# CAN-Bus_Shield_v1_2.net
KiCad netlist of a schematic drawn in EAGLE
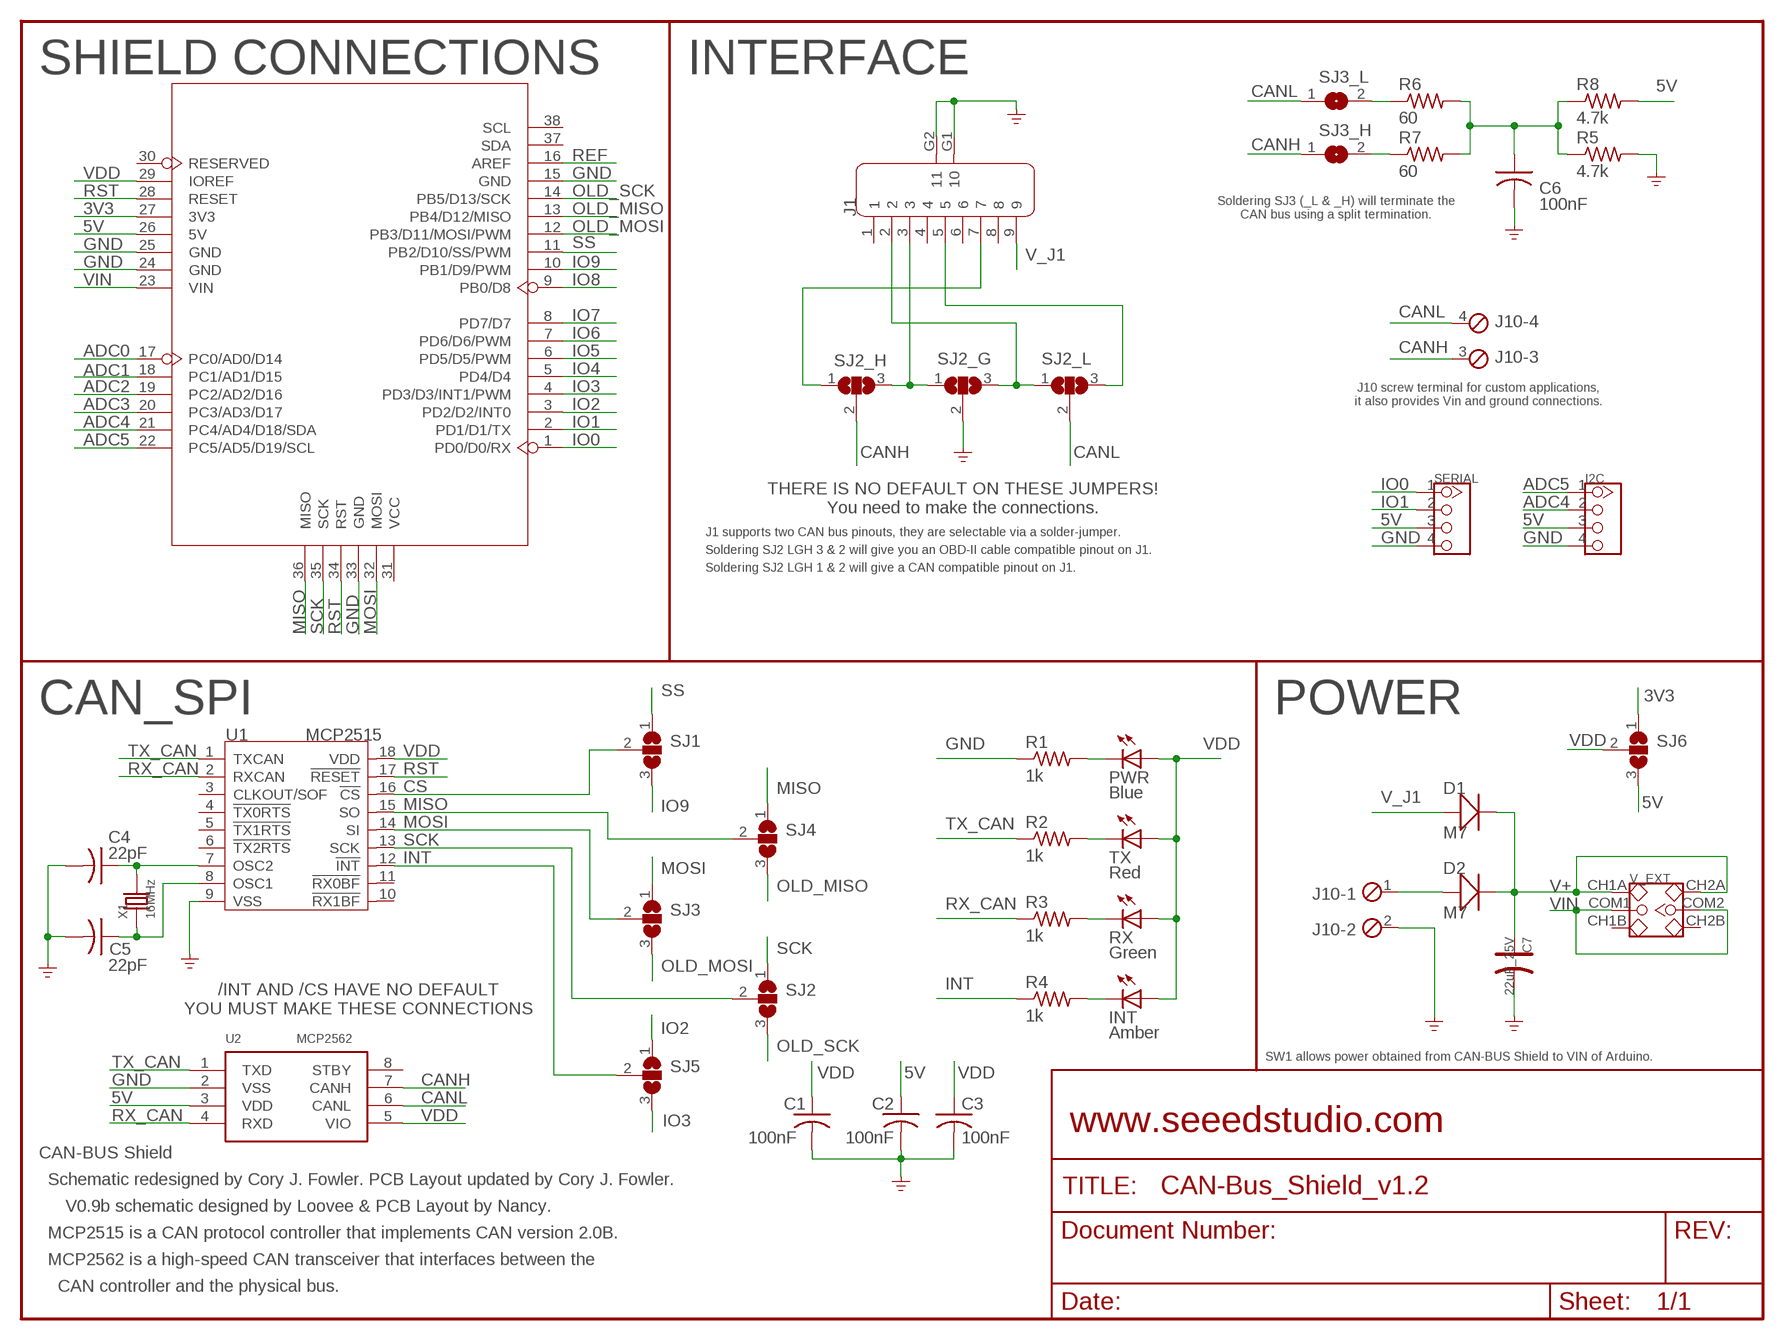
[diagram p0: schematic, sheet 1]

(export (version "E")
  (design (tool "Eeschema 10.0.6"))
  (components
    (comp (ref "C1")
      (value "100nF")
      (footprint "eagle-import:C0603K")
      (libsource (lib "eagle-import") (part "C-USC0603K"))
    )
    (comp (ref "C2")
      (value "100nF")
      (footprint "eagle-import:C0603K")
      (libsource (lib "eagle-import") (part "C-USC0603K"))
    )
    (comp (ref "C3")
      (value "100nF")
      (footprint "eagle-import:C0603K")
      (libsource (lib "eagle-import") (part "C-USC0603K"))
    )
    (comp (ref "C4")
      (value "22pF")
      (footprint "eagle-import:C0603")
      (libsource (lib "eagle-import") (part "C-USC0603"))
    )
    (comp (ref "C5")
      (value "22pF")
      (footprint "eagle-import:C0603")
      (libsource (lib "eagle-import") (part "C-USC0603"))
    )
    (comp (ref "C6")
      (value "100nF")
      (footprint "eagle-import:C1210")
      (libsource (lib "eagle-import") (part "C-USC1210"))
    )
    (comp (ref "C7")
      (value "22uF_25V")
      (footprint "eagle-import:AVX-C")
      (libsource (lib "eagle-import") (part "CAP-AVX-C"))
    )
    (comp (ref "D1")
      (value "M7")
      (footprint "eagle-import:D2010")
      (libsource (lib "eagle-import") (part "D-SMA"))
    )
    (comp (ref "D2")
      (value "M7")
      (footprint "eagle-import:D2010")
      (libsource (lib "eagle-import") (part "D-SMA"))
    )
    (comp (ref "I2C")
      (value "TWIG-4P-2.0-2.0")
      (footprint "eagle-import:4P-2.0")
      (libsource (lib "eagle-import") (part "TWIG-4P-2.0-2.0"))
    )
    (comp (ref "INT")
      (value "Amber")
      (footprint "eagle-import:CHIP-LED0805")
      (libsource (lib "eagle-import") (part "LEDCHIP-LED0805"))
    )
    (comp (ref "J1")
      (value "DB9'MEAL'")
      (footprint "eagle-import:DB9-MEAL")
      (libsource (lib "eagle-import") (part "DB9'MEAL'"))
    )
    (comp (ref "J10")
      (value "MPT4")
      (footprint "eagle-import:4POL254")
      (libsource (lib "eagle-import") (part "MPT4"))
    )
    (comp (ref "PWR")
      (value "Blue")
      (footprint "eagle-import:CHIP-LED0805")
      (libsource (lib "eagle-import") (part "LEDCHIP-LED0805"))
    )
    (comp (ref "R1")
      (value "1k")
      (footprint "eagle-import:M0805")
      (libsource (lib "eagle-import") (part "R-US_M0805"))
    )
    (comp (ref "R2")
      (value "1k")
      (footprint "eagle-import:M0805")
      (libsource (lib "eagle-import") (part "R-US_M0805"))
    )
    (comp (ref "R3")
      (value "1k")
      (footprint "eagle-import:M0805")
      (libsource (lib "eagle-import") (part "R-US_M0805"))
    )
    (comp (ref "R4")
      (value "1k")
      (footprint "eagle-import:M0805")
      (libsource (lib "eagle-import") (part "R-US_M0805"))
    )
    (comp (ref "R5")
      (value "4.7k")
      (footprint "eagle-import:M3216")
      (libsource (lib "eagle-import") (part "R-US_M3216"))
    )
    (comp (ref "R6")
      (value "60")
      (footprint "eagle-import:M3216")
      (libsource (lib "eagle-import") (part "R-US_M3216"))
    )
    (comp (ref "R7")
      (value "60")
      (footprint "eagle-import:M3216")
      (libsource (lib "eagle-import") (part "R-US_M3216"))
    )
    (comp (ref "R8")
      (value "4.7k")
      (footprint "eagle-import:M3216")
      (libsource (lib "eagle-import") (part "R-US_M3216"))
    )
    (comp (ref "RX")
      (value "Green")
      (footprint "eagle-import:CHIP-LED0805")
      (libsource (lib "eagle-import") (part "LEDCHIP-LED0805"))
    )
    (comp (ref "SERIAL")
      (value "TWIG-4P-2.0-2.0")
      (footprint "eagle-import:4P-2.0")
      (libsource (lib "eagle-import") (part "TWIG-4P-2.0-2.0"))
    )
    (comp (ref "SJ1")
      (value "SJ2W")
      (footprint "eagle-import:SJ_2")
      (libsource (lib "eagle-import") (part "SJ2W"))
    )
    (comp (ref "SJ2")
      (value "SJ2W")
      (footprint "eagle-import:SJ_2")
      (libsource (lib "eagle-import") (part "SJ2W"))
    )
    (comp (ref "SJ2_G")
      (value "SJ2W")
      (footprint "eagle-import:SJ_2")
      (libsource (lib "eagle-import") (part "SJ2W"))
    )
    (comp (ref "SJ2_H")
      (value "SJ2W")
      (footprint "eagle-import:SJ_2")
      (libsource (lib "eagle-import") (part "SJ2W"))
    )
    (comp (ref "SJ2_L")
      (value "SJ2W")
      (footprint "eagle-import:SJ_2")
      (libsource (lib "eagle-import") (part "SJ2W"))
    )
    (comp (ref "SJ3")
      (value "SJ2W")
      (footprint "eagle-import:SJ_2")
      (libsource (lib "eagle-import") (part "SJ2W"))
    )
    (comp (ref "SJ3_H")
      (value "SJ")
      (footprint "eagle-import:SJ")
      (libsource (lib "eagle-import") (part "SJ"))
    )
    (comp (ref "SJ3_L")
      (value "SJ")
      (footprint "eagle-import:SJ")
      (libsource (lib "eagle-import") (part "SJ"))
    )
    (comp (ref "SJ4")
      (value "SJ2W")
      (footprint "eagle-import:SJ_2")
      (libsource (lib "eagle-import") (part "SJ2W"))
    )
    (comp (ref "SJ5")
      (value "SJ2W")
      (footprint "eagle-import:SJ_2")
      (libsource (lib "eagle-import") (part "SJ2W"))
    )
    (comp (ref "SJ6")
      (value "SJ2W")
      (footprint "eagle-import:SJ_2")
      (libsource (lib "eagle-import") (part "SJ2W"))
    )
    (comp (ref "TX")
      (value "Red")
      (footprint "eagle-import:CHIP-LED0805")
      (libsource (lib "eagle-import") (part "LEDCHIP-LED0805"))
    )
    (comp (ref "U1")
      (value "MCP2515")
      (footprint "eagle-import:SOIC18")
      (libsource (lib "eagle-import") (part "MCP2515"))
    )
    (comp (ref "U2")
      (value "MCP2562")
      (footprint "eagle-import:SO08")
      (libsource (lib "eagle-import") (part "MCP2562"))
    )
    (comp (ref "U3")
      (value "ARDUINO")
      (footprint "eagle-import:ARDUINO")
      (libsource (lib "eagle-import") (part "ARDUINO"))
    )
    (comp (ref "V_EXT")
      (value "SWITCH-2CH-6P")
      (footprint "eagle-import:6P-2CH-2.54-7.6X3.0")
      (libsource (lib "eagle-import") (part "SWITCH-2CH-6P"))
    )
    (comp (ref "X1")
      (value "16MHz")
      (footprint "eagle-import:HC49_S")
      (libsource (lib "eagle-import") (part "CRYSTAL-HC49S"))
    )
  )
  (nets
    (net (code "1") (name "/3V3") (class "Default")
      (node (ref "SJ6") (pin "1") (pinfunction "1_1") (pintype "passive"))
      (node (ref "U3") (pin "27") (pinfunction "3V3_27") (pintype "bidirectional"))
    )
    (net (code "2") (name "/5V") (class "Default")
      (node (ref "C2") (pin "1") (pinfunction "1_1") (pintype "passive"))
      (node (ref "I2C") (pin "3") (pinfunction "3_3") (pintype "bidirectional"))
      (node (ref "R8") (pin "2") (pinfunction "2_2") (pintype "passive"))
      (node (ref "SERIAL") (pin "3") (pinfunction "3_3") (pintype "bidirectional"))
      (node (ref "SJ6") (pin "3") (pinfunction "3_3") (pintype "passive"))
      (node (ref "U2") (pin "3") (pinfunction "VDD_3") (pintype "bidirectional"))
      (node (ref "U3") (pin "26") (pinfunction "5V_26") (pintype "bidirectional"))
    )
    (net (code "3") (name "/ADC0") (class "Default")
      (node (ref "U3") (pin "17") (pinfunction "PC0/AD0/D14_17") (pintype "bidirectional"))
    )
    (net (code "4") (name "/ADC1") (class "Default")
      (node (ref "U3") (pin "18") (pinfunction "PC1/AD1/D15_18") (pintype "bidirectional"))
    )
    (net (code "5") (name "/ADC2") (class "Default")
      (node (ref "U3") (pin "19") (pinfunction "PC2/AD2/D16_19") (pintype "bidirectional"))
    )
    (net (code "6") (name "/ADC3") (class "Default")
      (node (ref "U3") (pin "20") (pinfunction "PC3/AD3/D17_20") (pintype "bidirectional"))
    )
    (net (code "7") (name "/ADC4") (class "Default")
      (node (ref "I2C") (pin "2") (pinfunction "2_2") (pintype "bidirectional"))
      (node (ref "U3") (pin "21") (pinfunction "PC4/AD4/D18/SDA_21") (pintype "bidirectional"))
    )
    (net (code "8") (name "/ADC5") (class "Default")
      (node (ref "I2C") (pin "1") (pinfunction "1_1") (pintype "bidirectional"))
      (node (ref "U3") (pin "22") (pinfunction "PC5/AD5/D19/SCL_22") (pintype "bidirectional"))
    )
    (net (code "9") (name "/CANH") (class "Default")
      (node (ref "J10") (pin "3") (pinfunction "1_3") (pintype "passive"))
      (node (ref "SJ2_H") (pin "2") (pinfunction "2_2") (pintype "passive"))
      (node (ref "SJ3_H") (pin "1") (pinfunction "1_1") (pintype "passive"))
      (node (ref "U2") (pin "7") (pinfunction "CANH_7") (pintype "bidirectional"))
    )
    (net (code "10") (name "/CANL") (class "Default")
      (node (ref "J10") (pin "4") (pinfunction "1_4") (pintype "passive"))
      (node (ref "SJ2_L") (pin "2") (pinfunction "2_2") (pintype "passive"))
      (node (ref "SJ3_L") (pin "1") (pinfunction "1_1") (pintype "passive"))
      (node (ref "U2") (pin "6") (pinfunction "CANL_6") (pintype "bidirectional"))
    )
    (net (code "11") (name "/CS") (class "Default")
      (node (ref "SJ1") (pin "2") (pinfunction "2_2") (pintype "passive"))
      (node (ref "U1") (pin "16") (pinfunction "~{CS}_16") (pintype "input"))
    )
    (net (code "12") (name "/INT") (class "Default")
      (node (ref "R4") (pin "1") (pinfunction "1_1") (pintype "passive"))
      (node (ref "SJ5") (pin "2") (pinfunction "2_2") (pintype "passive"))
      (node (ref "U1") (pin "12") (pinfunction "~{INT}_12") (pintype "output"))
    )
    (net (code "13") (name "/IO0") (class "Default")
      (node (ref "SERIAL") (pin "1") (pinfunction "1_1") (pintype "bidirectional"))
      (node (ref "U3") (pin "1") (pinfunction "PD0/D0/RX_1") (pintype "bidirectional"))
    )
    (net (code "14") (name "/IO1") (class "Default")
      (node (ref "SERIAL") (pin "2") (pinfunction "2_2") (pintype "bidirectional"))
      (node (ref "U3") (pin "2") (pinfunction "PD1/D1/TX_2") (pintype "bidirectional"))
    )
    (net (code "15") (name "/IO2") (class "Default")
      (node (ref "SJ5") (pin "1") (pinfunction "1_1") (pintype "passive"))
      (node (ref "U3") (pin "3") (pinfunction "PD2/D2/INT0_3") (pintype "bidirectional"))
    )
    (net (code "16") (name "/IO3") (class "Default")
      (node (ref "SJ5") (pin "3") (pinfunction "3_3") (pintype "passive"))
      (node (ref "U3") (pin "4") (pinfunction "PD3/D3/INT1/PWM_4") (pintype "bidirectional"))
    )
    (net (code "17") (name "/IO4") (class "Default")
      (node (ref "U3") (pin "5") (pinfunction "PD4/D4_5") (pintype "bidirectional"))
    )
    (net (code "18") (name "/IO5") (class "Default")
      (node (ref "U3") (pin "6") (pinfunction "PD5/D5/PWM_6") (pintype "bidirectional"))
    )
    (net (code "19") (name "/IO6") (class "Default")
      (node (ref "U3") (pin "7") (pinfunction "PD6/D6/PWM_7") (pintype "bidirectional"))
    )
    (net (code "20") (name "/IO7") (class "Default")
      (node (ref "U3") (pin "8") (pinfunction "PD7/D7_8") (pintype "bidirectional"))
    )
    (net (code "21") (name "/IO8") (class "Default")
      (node (ref "U3") (pin "9") (pinfunction "PB0/D8_9") (pintype "bidirectional"))
    )
    (net (code "22") (name "/IO9") (class "Default")
      (node (ref "SJ1") (pin "3") (pinfunction "3_3") (pintype "passive"))
      (node (ref "U3") (pin "10") (pinfunction "PB1/D9/PWM_10") (pintype "bidirectional"))
    )
    (net (code "23") (name "/MISO") (class "Default")
      (node (ref "SJ4") (pin "1") (pinfunction "1_1") (pintype "passive"))
      (node (ref "SJ4") (pin "2") (pinfunction "2_2") (pintype "passive"))
      (node (ref "U1") (pin "15") (pinfunction "SO_15") (pintype "output"))
      (node (ref "U3") (pin "36") (pinfunction "MISO_36") (pintype "bidirectional"))
    )
    (net (code "24") (name "/MOSI") (class "Default")
      (node (ref "SJ3") (pin "1") (pinfunction "1_1") (pintype "passive"))
      (node (ref "SJ3") (pin "2") (pinfunction "2_2") (pintype "passive"))
      (node (ref "U1") (pin "14") (pinfunction "SI_14") (pintype "input"))
      (node (ref "U3") (pin "32") (pinfunction "MOSI_32") (pintype "bidirectional"))
    )
    (net (code "25") (name "/OLD_MISO") (class "Default")
      (node (ref "SJ4") (pin "3") (pinfunction "3_3") (pintype "passive"))
      (node (ref "U3") (pin "13") (pinfunction "PB4/D12/MISO_13") (pintype "bidirectional"))
    )
    (net (code "26") (name "/OLD_MOSI") (class "Default")
      (node (ref "SJ3") (pin "3") (pinfunction "3_3") (pintype "passive"))
      (node (ref "U3") (pin "12") (pinfunction "PB3/D11/MOSI/PWM_12") (pintype "bidirectional"))
    )
    (net (code "27") (name "/OLD_SCK") (class "Default")
      (node (ref "SJ2") (pin "3") (pinfunction "3_3") (pintype "passive"))
      (node (ref "U3") (pin "14") (pinfunction "PB5/D13/SCK_14") (pintype "bidirectional"))
    )
    (net (code "28") (name "/REF") (class "Default")
      (node (ref "U3") (pin "16") (pinfunction "AREF_16") (pintype "bidirectional"))
    )
    (net (code "29") (name "/RST") (class "Default")
      (node (ref "U1") (pin "17") (pinfunction "~{RESET}_17") (pintype "input"))
      (node (ref "U3") (pin "28") (pinfunction "RESET_28") (pintype "bidirectional"))
      (node (ref "U3") (pin "34") (pinfunction "RST_34") (pintype "bidirectional"))
    )
    (net (code "30") (name "/RX_CAN") (class "Default")
      (node (ref "R3") (pin "1") (pinfunction "1_1") (pintype "passive"))
      (node (ref "U1") (pin "2") (pinfunction "RXCAN_2") (pintype "input"))
      (node (ref "U2") (pin "4") (pinfunction "RXD_4") (pintype "bidirectional"))
    )
    (net (code "31") (name "/SCK") (class "Default")
      (node (ref "SJ2") (pin "1") (pinfunction "1_1") (pintype "passive"))
      (node (ref "SJ2") (pin "2") (pinfunction "2_2") (pintype "passive"))
      (node (ref "U1") (pin "13") (pinfunction "SCK_13") (pintype "input"))
      (node (ref "U3") (pin "35") (pinfunction "SCK_35") (pintype "bidirectional"))
    )
    (net (code "32") (name "/SS") (class "Default")
      (node (ref "SJ1") (pin "1") (pinfunction "1_1") (pintype "passive"))
      (node (ref "U3") (pin "11") (pinfunction "PB2/D10/SS/PWM_11") (pintype "bidirectional"))
    )
    (net (code "33") (name "/TX_CAN") (class "Default")
      (node (ref "R2") (pin "1") (pinfunction "1_1") (pintype "passive"))
      (node (ref "U1") (pin "1") (pinfunction "TXCAN_1") (pintype "output"))
      (node (ref "U2") (pin "1") (pinfunction "TXD_1") (pintype "bidirectional"))
    )
    (net (code "34") (name "/V+") (class "Default")
      (node (ref "C7") (pin "+") (pinfunction "+_+") (pintype "passive"))
      (node (ref "D1") (pin "-") (pinfunction "-_-") (pintype "passive"))
      (node (ref "D2") (pin "-") (pinfunction "-_-") (pintype "passive"))
      (node (ref "V_EXT") (pin "CH1A") (pinfunction "CH1A_CH1A") (pintype "bidirectional"))
      (node (ref "V_EXT") (pin "CH2A") (pinfunction "CH2A_CH2A") (pintype "bidirectional"))
    )
    (net (code "35") (name "/VDD") (class "Default")
      (node (ref "C1") (pin "1") (pinfunction "1_1") (pintype "passive"))
      (node (ref "C3") (pin "1") (pinfunction "1_1") (pintype "passive"))
      (node (ref "INT") (pin "A") (pinfunction "A_A") (pintype "passive"))
      (node (ref "PWR") (pin "A") (pinfunction "A_A") (pintype "passive"))
      (node (ref "RX") (pin "A") (pinfunction "A_A") (pintype "passive"))
      (node (ref "SJ6") (pin "2") (pinfunction "2_2") (pintype "passive"))
      (node (ref "TX") (pin "A") (pinfunction "A_A") (pintype "passive"))
      (node (ref "U1") (pin "18") (pinfunction "VDD_18") (pintype "power_in"))
      (node (ref "U2") (pin "5") (pinfunction "VIO_5") (pintype "bidirectional"))
      (node (ref "U3") (pin "29") (pinfunction "IOREF_29") (pintype "bidirectional"))
    )
    (net (code "36") (name "/VIN") (class "Default")
      (node (ref "U3") (pin "23") (pinfunction "VIN_23") (pintype "bidirectional"))
      (node (ref "V_EXT") (pin "COM1") (pinfunction "COM1_COM1") (pintype "bidirectional"))
      (node (ref "V_EXT") (pin "COM2") (pinfunction "COM2_COM2") (pintype "bidirectional"))
    )
    (net (code "37") (name "/V_J1") (class "Default")
      (node (ref "D1") (pin "+") (pinfunction "+_+") (pintype "passive"))
      (node (ref "J1") (pin "9") (pinfunction "9_9") (pintype "bidirectional"))
    )
    (net (code "38") (name "GND_POWER") (class "Default")
      (node (ref "C1") (pin "2") (pinfunction "2_2") (pintype "passive"))
      (node (ref "C2") (pin "2") (pinfunction "2_2") (pintype "passive"))
      (node (ref "C3") (pin "2") (pinfunction "2_2") (pintype "passive"))
      (node (ref "C4") (pin "2") (pinfunction "2_2") (pintype "passive"))
      (node (ref "C5") (pin "2") (pinfunction "2_2") (pintype "passive"))
      (node (ref "C6") (pin "2") (pinfunction "2_2") (pintype "passive"))
      (node (ref "C7") (pin "-") (pinfunction "-_-") (pintype "passive"))
      (node (ref "I2C") (pin "4") (pinfunction "4_4") (pintype "bidirectional"))
      (node (ref "J1") (pin "G1") (pinfunction "10_G1") (pintype "bidirectional"))
      (node (ref "J1") (pin "G2") (pinfunction "11_G2") (pintype "bidirectional"))
      (node (ref "J10") (pin "2") (pinfunction "1_2") (pintype "passive"))
      (node (ref "R1") (pin "1") (pinfunction "1_1") (pintype "passive"))
      (node (ref "R5") (pin "2") (pinfunction "2_2") (pintype "passive"))
      (node (ref "SERIAL") (pin "4") (pinfunction "4_4") (pintype "bidirectional"))
      (node (ref "SJ2_G") (pin "2") (pinfunction "2_2") (pintype "passive"))
      (node (ref "U1") (pin "9") (pinfunction "VSS_9") (pintype "power_in"))
      (node (ref "U2") (pin "2") (pinfunction "VSS_2") (pintype "bidirectional"))
      (node (ref "U3") (pin "15") (pinfunction "GND_15") (pintype "bidirectional"))
      (node (ref "U3") (pin "24") (pinfunction "GND_24") (pintype "bidirectional"))
      (node (ref "U3") (pin "25") (pinfunction "GND_25") (pintype "bidirectional"))
      (node (ref "U3") (pin "33") (pinfunction "GND_33") (pintype "bidirectional"))
    )
    (net (code "39") (name "Net-(C6-Pad1)") (class "Default")
      (node (ref "C6") (pin "1") (pinfunction "1_1") (pintype "passive"))
      (node (ref "R5") (pin "1") (pinfunction "1_1") (pintype "passive"))
      (node (ref "R6") (pin "2") (pinfunction "2_2") (pintype "passive"))
      (node (ref "R7") (pin "2") (pinfunction "2_2") (pintype "passive"))
      (node (ref "R8") (pin "1") (pinfunction "1_1") (pintype "passive"))
    )
    (net (code "40") (name "Net-(D2-Pad+)") (class "Default")
      (node (ref "D2") (pin "+") (pinfunction "+_+") (pintype "passive"))
      (node (ref "J10") (pin "1") (pinfunction "1_1") (pintype "passive"))
    )
    (net (code "41") (name "Net-(INT-PadC)") (class "Default")
      (node (ref "INT") (pin "C") (pinfunction "C_C") (pintype "passive"))
      (node (ref "R4") (pin "2") (pinfunction "2_2") (pintype "passive"))
    )
    (net (code "42") (name "Net-(J1-Pad2)") (class "Default")
      (node (ref "J1") (pin "2") (pinfunction "2_2") (pintype "bidirectional"))
      (node (ref "SJ2_G") (pin "3") (pinfunction "3_3") (pintype "passive"))
      (node (ref "SJ2_L") (pin "1") (pinfunction "1_1") (pintype "passive"))
    )
    (net (code "43") (name "Net-(J1-Pad3)") (class "Default")
      (node (ref "J1") (pin "3") (pinfunction "3_3") (pintype "bidirectional"))
      (node (ref "SJ2_G") (pin "1") (pinfunction "1_1") (pintype "passive"))
      (node (ref "SJ2_H") (pin "3") (pinfunction "3_3") (pintype "passive"))
    )
    (net (code "44") (name "Net-(J1-Pad5)") (class "Default")
      (node (ref "J1") (pin "5") (pinfunction "5_5") (pintype "bidirectional"))
      (node (ref "SJ2_L") (pin "3") (pinfunction "3_3") (pintype "passive"))
    )
    (net (code "45") (name "Net-(J1-Pad7)") (class "Default")
      (node (ref "J1") (pin "7") (pinfunction "7_7") (pintype "bidirectional"))
      (node (ref "SJ2_H") (pin "1") (pinfunction "1_1") (pintype "passive"))
    )
    (net (code "46") (name "Net-(PWR-PadC)") (class "Default")
      (node (ref "PWR") (pin "C") (pinfunction "C_C") (pintype "passive"))
      (node (ref "R1") (pin "2") (pinfunction "2_2") (pintype "passive"))
    )
    (net (code "47") (name "Net-(R2-Pad2)") (class "Default")
      (node (ref "R2") (pin "2") (pinfunction "2_2") (pintype "passive"))
      (node (ref "TX") (pin "C") (pinfunction "C_C") (pintype "passive"))
    )
    (net (code "48") (name "Net-(R3-Pad2)") (class "Default")
      (node (ref "R3") (pin "2") (pinfunction "2_2") (pintype "passive"))
      (node (ref "RX") (pin "C") (pinfunction "C_C") (pintype "passive"))
    )
    (net (code "49") (name "Net-(R6-Pad1)") (class "Default")
      (node (ref "R6") (pin "1") (pinfunction "1_1") (pintype "passive"))
      (node (ref "SJ3_L") (pin "2") (pinfunction "2_2") (pintype "passive"))
    )
    (net (code "50") (name "Net-(R7-Pad1)") (class "Default")
      (node (ref "R7") (pin "1") (pinfunction "1_1") (pintype "passive"))
      (node (ref "SJ3_H") (pin "2") (pinfunction "2_2") (pintype "passive"))
    )
    (net (code "51") (name "Net-(U1-OSC1)") (class "Default")
      (node (ref "C5") (pin "1") (pinfunction "1_1") (pintype "passive"))
      (node (ref "U1") (pin "8") (pinfunction "OSC1_8") (pintype "input"))
      (node (ref "X1") (pin "1") (pinfunction "1_1") (pintype "passive"))
    )
    (net (code "52") (name "Net-(U1-OSC2)") (class "Default")
      (node (ref "C4") (pin "1") (pinfunction "1_1") (pintype "passive"))
      (node (ref "U1") (pin "7") (pinfunction "OSC2_7") (pintype "output"))
      (node (ref "X1") (pin "2") (pinfunction "2_2") (pintype "passive"))
    )
    (net (code "53") (name "unconnected-(J1-Pad1)") (class "Default")
      (node (ref "J1") (pin "1") (pinfunction "1_1") (pintype "bidirectional"))
    )
    (net (code "54") (name "unconnected-(J1-Pad4)") (class "Default")
      (node (ref "J1") (pin "4") (pinfunction "4_4") (pintype "bidirectional"))
    )
    (net (code "55") (name "unconnected-(J1-Pad6)") (class "Default")
      (node (ref "J1") (pin "6") (pinfunction "6_6") (pintype "bidirectional"))
    )
    (net (code "56") (name "unconnected-(J1-Pad8)") (class "Default")
      (node (ref "J1") (pin "8") (pinfunction "8_8") (pintype "bidirectional"))
    )
    (net (code "57") (name "unconnected-(U1-CLKOUT{slash}SOF-Pad3)") (class "Default")
      (node (ref "U1") (pin "3") (pinfunction "CLKOUT/SOF_3") (pintype "output"))
    )
    (net (code "58") (name "unconnected-(U1-~{RX0BF}-Pad11)") (class "Default")
      (node (ref "U1") (pin "11") (pinfunction "~{RX0BF}_11") (pintype "output"))
    )
    (net (code "59") (name "unconnected-(U1-~{RX1BF}-Pad10)") (class "Default")
      (node (ref "U1") (pin "10") (pinfunction "~{RX1BF}_10") (pintype "output"))
    )
    (net (code "60") (name "unconnected-(U1-~{TX0RTS}-Pad4)") (class "Default")
      (node (ref "U1") (pin "4") (pinfunction "~{TX0RTS}_4") (pintype "input"))
    )
    (net (code "61") (name "unconnected-(U1-~{TX1RTS}-Pad5)") (class "Default")
      (node (ref "U1") (pin "5") (pinfunction "~{TX1RTS}_5") (pintype "input"))
    )
    (net (code "62") (name "unconnected-(U1-~{TX2RTS}-Pad6)") (class "Default")
      (node (ref "U1") (pin "6") (pinfunction "~{TX2RTS}_6") (pintype "input"))
    )
    (net (code "63") (name "unconnected-(U2-STBY-Pad8)") (class "Default")
      (node (ref "U2") (pin "8") (pinfunction "STBY_8") (pintype "bidirectional"))
    )
    (net (code "64") (name "unconnected-(U3-RESERVED-Pad30)") (class "Default")
      (node (ref "U3") (pin "30") (pinfunction "RESERVED_30") (pintype "no_connect"))
    )
    (net (code "65") (name "unconnected-(U3-SCL-Pad38)") (class "Default")
      (node (ref "U3") (pin "38") (pinfunction "SCL_38") (pintype "bidirectional"))
    )
    (net (code "66") (name "unconnected-(U3-SDA-Pad37)") (class "Default")
      (node (ref "U3") (pin "37") (pinfunction "SDA_37") (pintype "bidirectional"))
    )
    (net (code "67") (name "unconnected-(U3-VCC-Pad31)") (class "Default")
      (node (ref "U3") (pin "31") (pinfunction "VCC_31") (pintype "bidirectional"))
    )
    (net (code "68") (name "unconnected-(V_EXT-PadCH1B)") (class "Default")
      (node (ref "V_EXT") (pin "CH1B") (pinfunction "CH1B_CH1B") (pintype "bidirectional"))
    )
    (net (code "69") (name "unconnected-(V_EXT-PadCH2B)") (class "Default")
      (node (ref "V_EXT") (pin "CH2B") (pinfunction "CH2B_CH2B") (pintype "bidirectional"))
    )
  )
)
